# design.net
KiCad netlist of a schematic drawn in Altium Designer
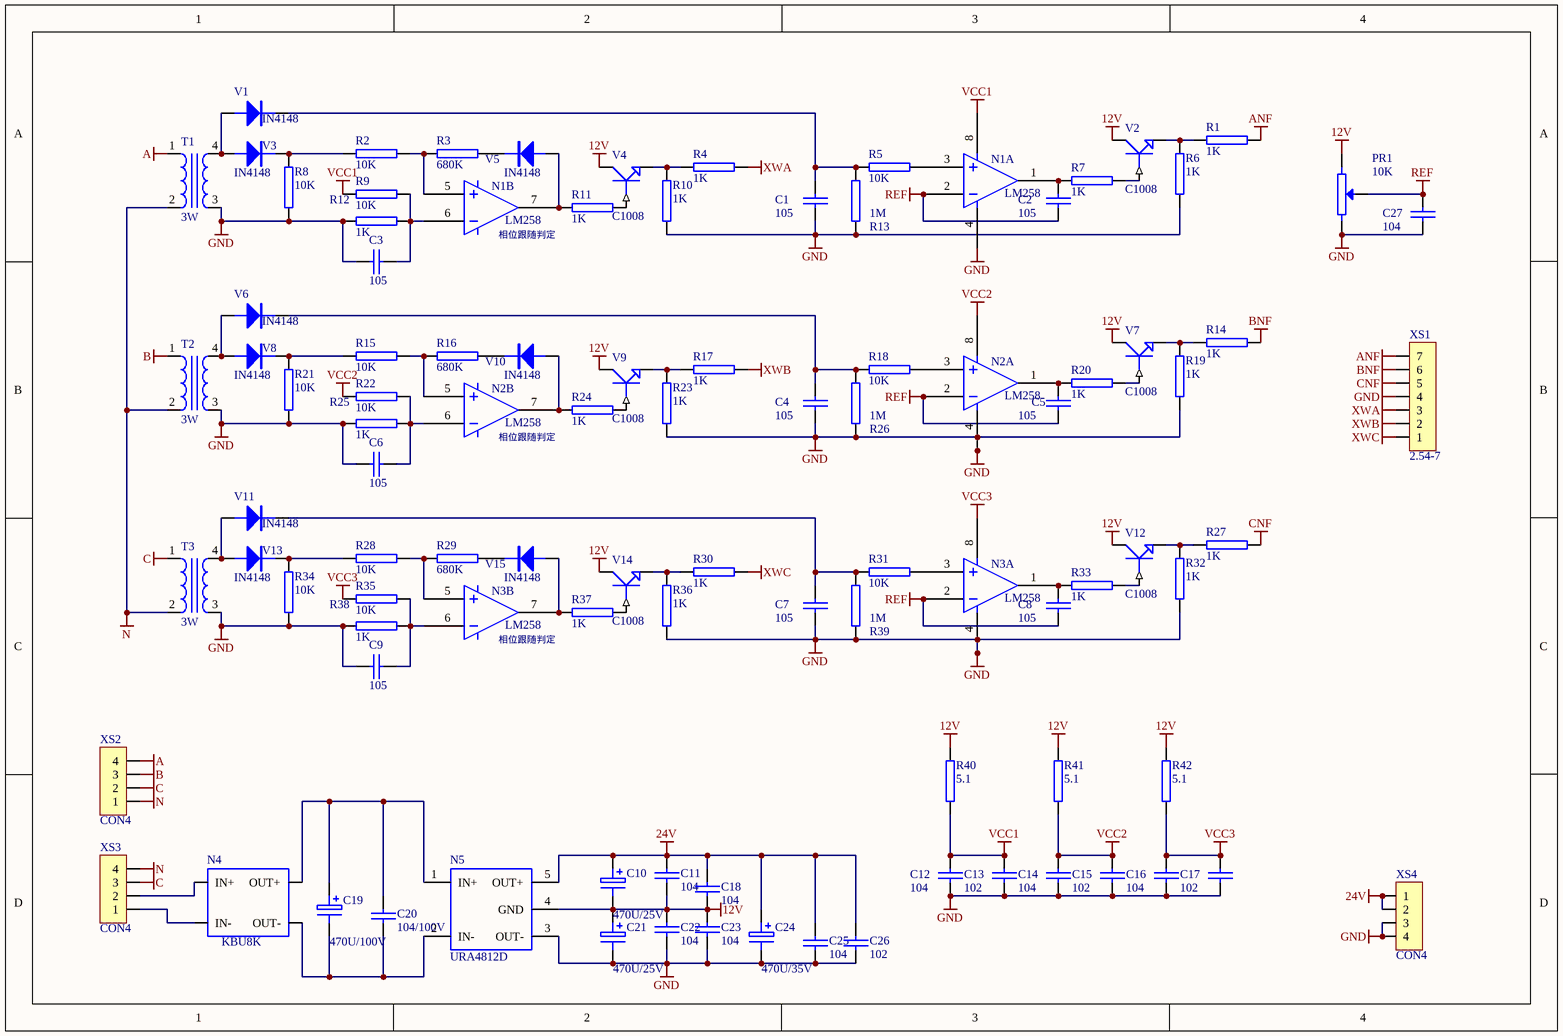
[diagram p0: 相位.SchDoc]

(export (version "E")
  (design (tool "Eeschema 10.0.6"))
  (components
    (comp (ref "C1") (value "105") (footprint "0805A") (libsource (lib "THT") (part "CAP")))
    (comp (ref "C2") (value "105") (footprint "0805A") (libsource (lib "THT") (part "CAP")))
    (comp (ref "C3") (value "105") (footprint "0805A") (libsource (lib "THT") (part "CAP")))
    (comp (ref "C4") (value "105") (footprint "0805A") (libsource (lib "THT") (part "CAP")))
    (comp (ref "C5") (value "105") (footprint "0805A") (libsource (lib "THT") (part "CAP")))
    (comp (ref "C6") (value "105") (footprint "0805A") (libsource (lib "THT") (part "CAP")))
    (comp (ref "C7") (value "105") (footprint "0805A") (libsource (lib "THT") (part "CAP")))
    (comp (ref "C8") (value "105") (footprint "0805A") (libsource (lib "THT") (part "CAP")))
    (comp (ref "C9") (value "105") (footprint "0805A") (libsource (lib "THT") (part "CAP")))
    (comp (ref "C10") (value "470U/25V") (footprint "RB5/10") (libsource (lib "*") (part "ELECTRO1")))
    (comp (ref "C11") (value "104") (footprint "1206") (libsource (lib "THT") (part "CAP")))
    (comp (ref "C12") (value "104") (footprint "0805A") (libsource (lib "THT") (part "CAP")))
    (comp (ref "C13") (value "102") (footprint "0805A") (libsource (lib "THT") (part "CAP")))
    (comp (ref "C14") (value "104") (footprint "0805A") (libsource (lib "THT") (part "CAP")))
    (comp (ref "C15") (value "102") (footprint "0805A") (libsource (lib "THT") (part "CAP")))
    (comp (ref "C16") (value "104") (footprint "0805A") (libsource (lib "THT") (part "CAP")))
    (comp (ref "C17") (value "102") (footprint "0805A") (libsource (lib "THT") (part "CAP")))
    (comp (ref "C18") (value "104") (footprint "1206") (libsource (lib "THT") (part "CAP")))
    (comp (ref "C19") (value "470U/100V") (footprint "RB.2/.6") (libsource (lib "*") (part "ELECTRO1")))
    (comp (ref "C20") (value "104/100V") (footprint "RAD0.2") (libsource (lib "THT") (part "CAP")))
    (comp (ref "C21") (value "470U/25V") (footprint "RB5/10") (libsource (lib "*") (part "ELECTRO1")))
    (comp (ref "C22") (value "104") (footprint "1206") (libsource (lib "THT") (part "CAP")))
    (comp (ref "C23") (value "104") (footprint "1206") (libsource (lib "THT") (part "CAP")))
    (comp (ref "C24") (value "470U/35V") (footprint "RB5/10") (libsource (lib "*") (part "ELECTRO1")))
    (comp (ref "C25") (value "104") (footprint "1206") (libsource (lib "THT") (part "CAP")))
    (comp (ref "C26") (value "102") (footprint "1206") (libsource (lib "THT") (part "CAP")))
    (comp (ref "C27") (value "104") (footprint "0805A") (libsource (lib "THT") (part "CAP")))
    (comp (ref "N1") (value "LM258") (footprint "SO-8") (libsource (lib "*") (part "LF353")))
    (comp (ref "N2") (value "LM258") (footprint "SO-8") (libsource (lib "*") (part "LF353")))
    (comp (ref "N3") (value "LM258") (footprint "SO-8") (libsource (lib "*") (part "LF353")))
    (comp (ref "N4") (value "KBU8K") (libsource (lib "THT") (part "DC-DC")))
    (comp (ref "N5") (value "URA4812D") (footprint "URA48") (libsource (lib "TH1") (part "YND5")))
    (comp (ref "PR1") (value "10K") (footprint "3224") (libsource (lib "TH1") (part "POT")))
    (comp (ref "R1") (value "1K") (footprint "0805A") (libsource (lib "THT") (part "RES2")))
    (comp (ref "R2") (value "10K") (footprint "0805A") (libsource (lib "THT") (part "RES2")))
    (comp (ref "R3") (value "680K") (footprint "0805A") (libsource (lib "THT") (part "RES2")))
    (comp (ref "R4") (value "1K") (footprint "0805A") (libsource (lib "THT") (part "RES2")))
    (comp (ref "R5") (value "10K") (footprint "0805A") (libsource (lib "THT") (part "RES2")))
    (comp (ref "R6") (value "1K") (footprint "0805A") (libsource (lib "THT") (part "RES2")))
    (comp (ref "R7") (value "1K") (footprint "0805A") (libsource (lib "THT") (part "RES2")))
    (comp (ref "R8") (value "10K") (footprint "0805A") (libsource (lib "THT") (part "RES2")))
    (comp (ref "R9") (value "10K") (footprint "0805A") (libsource (lib "THT") (part "RES2")))
    (comp (ref "R10") (value "1K") (footprint "0805A") (libsource (lib "THT") (part "RES2")))
    (comp (ref "R11") (value "1K") (footprint "0805A") (libsource (lib "THT") (part "RES2")))
    (comp (ref "R12") (value "1K") (footprint "0805A") (libsource (lib "THT") (part "RES2")))
    (comp (ref "R13") (value "1M") (footprint "0805A") (libsource (lib "THT") (part "RES2")))
    (comp (ref "R14") (value "1K") (footprint "0805A") (libsource (lib "THT") (part "RES2")))
    (comp (ref "R15") (value "10K") (footprint "0805A") (libsource (lib "THT") (part "RES2")))
    (comp (ref "R16") (value "680K") (footprint "0805A") (libsource (lib "THT") (part "RES2")))
    (comp (ref "R17") (value "1K") (footprint "0805A") (libsource (lib "THT") (part "RES2")))
    (comp (ref "R18") (value "10K") (footprint "0805A") (libsource (lib "THT") (part "RES2")))
    (comp (ref "R19") (value "1K") (footprint "0805A") (libsource (lib "THT") (part "RES2")))
    (comp (ref "R20") (value "1K") (footprint "0805A") (libsource (lib "THT") (part "RES2")))
    (comp (ref "R21") (value "10K") (footprint "0805A") (libsource (lib "THT") (part "RES2")))
    (comp (ref "R22") (value "10K") (footprint "0805A") (libsource (lib "THT") (part "RES2")))
    (comp (ref "R23") (value "1K") (footprint "0805A") (libsource (lib "THT") (part "RES2")))
    (comp (ref "R24") (value "1K") (footprint "0805A") (libsource (lib "THT") (part "RES2")))
    (comp (ref "R25") (value "1K") (footprint "0805A") (libsource (lib "THT") (part "RES2")))
    (comp (ref "R26") (value "1M") (footprint "0805A") (libsource (lib "THT") (part "RES2")))
    (comp (ref "R27") (value "1K") (footprint "0805A") (libsource (lib "THT") (part "RES2")))
    (comp (ref "R28") (value "10K") (footprint "0805A") (libsource (lib "THT") (part "RES2")))
    (comp (ref "R29") (value "680K") (footprint "0805A") (libsource (lib "THT") (part "RES2")))
    (comp (ref "R30") (value "1K") (footprint "0805A") (libsource (lib "THT") (part "RES2")))
    (comp (ref "R31") (value "10K") (footprint "0805A") (libsource (lib "THT") (part "RES2")))
    (comp (ref "R32") (value "1K") (footprint "0805A") (libsource (lib "THT") (part "RES2")))
    (comp (ref "R33") (value "1K") (footprint "0805A") (libsource (lib "THT") (part "RES2")))
    (comp (ref "R34") (value "10K") (footprint "0805A") (libsource (lib "THT") (part "RES2")))
    (comp (ref "R35") (value "10K") (footprint "0805A") (libsource (lib "THT") (part "RES2")))
    (comp (ref "R36") (value "1K") (footprint "0805A") (libsource (lib "THT") (part "RES2")))
    (comp (ref "R37") (value "1K") (footprint "0805A") (libsource (lib "THT") (part "RES2")))
    (comp (ref "R38") (value "1K") (footprint "0805A") (libsource (lib "THT") (part "RES2")))
    (comp (ref "R39") (value "1M") (footprint "0805A") (libsource (lib "THT") (part "RES2")))
    (comp (ref "R40") (value "5.1") (footprint "0805A") (libsource (lib "THT") (part "RES2")))
    (comp (ref "R41") (value "5.1") (footprint "0805A") (libsource (lib "THT") (part "RES2")))
    (comp (ref "R42") (value "5.1") (footprint "0805A") (libsource (lib "THT") (part "RES2")))
    (comp (ref "T1") (value "3W") (footprint "EE35") (libsource (lib "TH1") (part "TRANS1")))
    (comp (ref "T2") (value "3W") (footprint "EE35") (libsource (lib "TH1") (part "TRANS1")))
    (comp (ref "T3") (value "3W") (footprint "EE35") (libsource (lib "TH1") (part "TRANS1")))
    (comp (ref "V1") (value "IN4148") (footprint "1206-D") (libsource (lib "THT") (part "DIODE1")))
    (comp (ref "V2") (value "C1008") (footprint "SOT-23") (libsource (lib "THT") (part "NPN1")))
    (comp (ref "V3") (value "IN4148") (footprint "1206-D") (libsource (lib "THT") (part "DIODE1")))
    (comp (ref "V4") (value "C1008") (footprint "SOT-23") (libsource (lib "THT") (part "NPN1")))
    (comp (ref "V5") (value "IN4148") (footprint "1206-D") (libsource (lib "THT") (part "DIODE1")))
    (comp (ref "V6") (value "IN4148") (footprint "1206-D") (libsource (lib "THT") (part "DIODE1")))
    (comp (ref "V7") (value "C1008") (footprint "SOT-23") (libsource (lib "THT") (part "NPN1")))
    (comp (ref "V8") (value "IN4148") (footprint "1206-D") (libsource (lib "THT") (part "DIODE1")))
    (comp (ref "V9") (value "C1008") (footprint "SOT-23") (libsource (lib "THT") (part "NPN1")))
    (comp (ref "V10") (value "IN4148") (footprint "1206-D") (libsource (lib "THT") (part "DIODE1")))
    (comp (ref "V11") (value "IN4148") (footprint "1206-D") (libsource (lib "THT") (part "DIODE1")))
    (comp (ref "V12") (value "C1008") (footprint "SOT-23") (libsource (lib "THT") (part "NPN1")))
    (comp (ref "V13") (value "IN4148") (footprint "1206-D") (libsource (lib "THT") (part "DIODE1")))
    (comp (ref "V14") (value "C1008") (footprint "SOT-23") (libsource (lib "THT") (part "NPN1")))
    (comp (ref "V15") (value "IN4148") (footprint "1206-D") (libsource (lib "THT") (part "DIODE1")))
    (comp (ref "XS1") (value "2.54-7") (footprint "SIP7") (libsource (lib "THT") (part "CON7")))
    (comp (ref "XS2") (value "CON4") (footprint "XS10A-4P") (libsource (lib "THT") (part "CON4")))
    (comp (ref "XS3") (value "CON4") (footprint "XS10A-4P") (libsource (lib "THT") (part "CON4")))
    (comp (ref "XS4") (value "CON4") (footprint "SIP4") (libsource (lib "") (part "CON4_1")))
  )
  (nets
    (net (code "1") (name "12V") (class "Default")
      (node (ref "C10") (pin "2") (pintype "passive"))
      (node (ref "C11") (pin "2") (pintype "passive"))
      (node (ref "C18") (pin "2") (pintype "passive"))
      (node (ref "C21") (pin "1") (pintype "passive"))
      (node (ref "C22") (pin "1") (pintype "passive"))
      (node (ref "C23") (pin "1") (pintype "passive"))
      (node (ref "N5") (pin "4") (pinfunction "GND_4") (pintype "passive"))
      (node (ref "PR1") (pin "2") (pinfunction "2_2") (pintype "passive"))
      (node (ref "R40") (pin "2") (pintype "passive"))
      (node (ref "R41") (pin "2") (pintype "passive"))
      (node (ref "R42") (pin "2") (pintype "passive"))
      (node (ref "V12") (pin "C") (pinfunction "C_C") (pintype "passive"))
      (node (ref "V14") (pin "C") (pinfunction "C_C") (pintype "passive"))
      (node (ref "V2") (pin "C") (pinfunction "C_C") (pintype "passive"))
      (node (ref "V4") (pin "C") (pinfunction "C_C") (pintype "passive"))
      (node (ref "V7") (pin "C") (pinfunction "C_C") (pintype "passive"))
      (node (ref "V9") (pin "C") (pinfunction "C_C") (pintype "passive"))
    )
    (net (code "2") (name "24V") (class "Default")
      (node (ref "C10") (pin "1") (pintype "passive"))
      (node (ref "C11") (pin "1") (pintype "passive"))
      (node (ref "C18") (pin "1") (pintype "passive"))
      (node (ref "C24") (pin "1") (pintype "passive"))
      (node (ref "C25") (pin "1") (pintype "passive"))
      (node (ref "C26") (pin "1") (pintype "passive"))
      (node (ref "N5") (pin "5") (pinfunction "OUT+_5") (pintype "passive"))
      (node (ref "XS4") (pin "1") (pinfunction "1_1") (pintype "passive"))
      (node (ref "XS4") (pin "2") (pinfunction "2_2") (pintype "passive"))
    )
    (net (code "3") (name "A") (class "Default")
      (node (ref "T1") (pin "1") (pinfunction "1_1") (pintype "passive"))
      (node (ref "XS2") (pin "4") (pinfunction "4_4") (pintype "passive"))
    )
    (net (code "4") (name "ANF") (class "Default")
      (node (ref "R1") (pin "2") (pintype "passive"))
      (node (ref "XS1") (pin "7") (pinfunction "7_7") (pintype "passive"))
    )
    (net (code "5") (name "B") (class "Default")
      (node (ref "T2") (pin "1") (pinfunction "1_1") (pintype "passive"))
      (node (ref "XS2") (pin "3") (pinfunction "3_3") (pintype "passive"))
    )
    (net (code "6") (name "BNF") (class "Default")
      (node (ref "R14") (pin "2") (pintype "passive"))
      (node (ref "XS1") (pin "6") (pinfunction "6_6") (pintype "passive"))
    )
    (net (code "7") (name "C") (class "Default")
      (node (ref "T3") (pin "1") (pinfunction "1_1") (pintype "passive"))
      (node (ref "XS2") (pin "2") (pinfunction "2_2") (pintype "passive"))
      (node (ref "XS3") (pin "3") (pinfunction "3_3") (pintype "passive"))
    )
    (net (code "8") (name "CNF") (class "Default")
      (node (ref "R27") (pin "2") (pintype "passive"))
      (node (ref "XS1") (pin "5") (pinfunction "5_5") (pintype "passive"))
    )
    (net (code "9") (name "GND") (class "Default")
      (node (ref "C1") (pin "1") (pintype "passive"))
      (node (ref "C12") (pin "1") (pintype "passive"))
      (node (ref "C13") (pin "1") (pintype "passive"))
      (node (ref "C14") (pin "1") (pintype "passive"))
      (node (ref "C15") (pin "1") (pintype "passive"))
      (node (ref "C16") (pin "1") (pintype "passive"))
      (node (ref "C17") (pin "1") (pintype "passive"))
      (node (ref "C21") (pin "2") (pintype "passive"))
      (node (ref "C22") (pin "2") (pintype "passive"))
      (node (ref "C23") (pin "2") (pintype "passive"))
      (node (ref "C24") (pin "2") (pintype "passive"))
      (node (ref "C25") (pin "2") (pintype "passive"))
      (node (ref "C26") (pin "2") (pintype "passive"))
      (node (ref "C27") (pin "1") (pintype "passive"))
      (node (ref "C3") (pin "2") (pintype "passive"))
      (node (ref "C4") (pin "1") (pintype "passive"))
      (node (ref "C6") (pin "2") (pintype "passive"))
      (node (ref "C7") (pin "1") (pintype "passive"))
      (node (ref "C9") (pin "2") (pintype "passive"))
      (node (ref "N1") (pin "4") (pintype "passive"))
      (node (ref "N2") (pin "4") (pintype "passive"))
      (node (ref "N3") (pin "4") (pintype "passive"))
      (node (ref "N5") (pin "3") (pinfunction "OUT-_3") (pintype "passive"))
      (node (ref "PR1") (pin "1") (pinfunction "1_1") (pintype "passive"))
      (node (ref "R10") (pin "1") (pintype "passive"))
      (node (ref "R12") (pin "1") (pintype "passive"))
      (node (ref "R13") (pin "2") (pintype "passive"))
      (node (ref "R19") (pin "1") (pintype "passive"))
      (node (ref "R21") (pin "1") (pintype "passive"))
      (node (ref "R23") (pin "1") (pintype "passive"))
      (node (ref "R25") (pin "1") (pintype "passive"))
      (node (ref "R26") (pin "2") (pintype "passive"))
      (node (ref "R32") (pin "1") (pintype "passive"))
      (node (ref "R34") (pin "1") (pintype "passive"))
      (node (ref "R36") (pin "1") (pintype "passive"))
      (node (ref "R38") (pin "1") (pintype "passive"))
      (node (ref "R39") (pin "2") (pintype "passive"))
      (node (ref "R6") (pin "1") (pintype "passive"))
      (node (ref "R8") (pin "1") (pintype "passive"))
      (node (ref "T1") (pin "3") (pinfunction "3_3") (pintype "passive"))
      (node (ref "T2") (pin "3") (pinfunction "3_3") (pintype "passive"))
      (node (ref "T3") (pin "3") (pinfunction "3_3") (pintype "passive"))
      (node (ref "XS1") (pin "4") (pinfunction "4_4") (pintype "passive"))
      (node (ref "XS4") (pin "3") (pinfunction "3_3") (pintype "passive"))
      (node (ref "XS4") (pin "4") (pinfunction "4_4") (pintype "passive"))
    )
    (net (code "10") (name "N") (class "Default")
      (node (ref "T1") (pin "2") (pinfunction "2_2") (pintype "passive"))
      (node (ref "T2") (pin "2") (pinfunction "2_2") (pintype "passive"))
      (node (ref "T3") (pin "2") (pinfunction "2_2") (pintype "passive"))
      (node (ref "XS2") (pin "1") (pinfunction "1_1") (pintype "passive"))
      (node (ref "XS3") (pin "4") (pinfunction "4_4") (pintype "passive"))
    )
    (net (code "11") (name "Net-(C1-Pad2)") (class "Default")
      (node (ref "C1") (pin "2") (pintype "passive"))
      (node (ref "R13") (pin "1") (pintype "passive"))
      (node (ref "R5") (pin "1") (pintype "passive"))
      (node (ref "V1") (pin "K") (pinfunction "K_K") (pintype "passive"))
    )
    (net (code "12") (name "Net-(C2-Pad2)") (class "Default")
      (node (ref "C2") (pin "2") (pintype "passive"))
      (node (ref "N1") (pin "1") (pintype "passive"))
      (node (ref "R7") (pin "1") (pintype "passive"))
    )
    (net (code "13") (name "Net-(C3-Pad1)") (class "Default")
      (node (ref "C3") (pin "1") (pintype "passive"))
      (node (ref "N1") (pin "6") (pintype "passive"))
      (node (ref "R12") (pin "2") (pintype "passive"))
      (node (ref "R9") (pin "2") (pintype "passive"))
    )
    (net (code "14") (name "Net-(C4-Pad2)") (class "Default")
      (node (ref "C4") (pin "2") (pintype "passive"))
      (node (ref "R18") (pin "1") (pintype "passive"))
      (node (ref "R26") (pin "1") (pintype "passive"))
      (node (ref "V6") (pin "K") (pinfunction "K_K") (pintype "passive"))
    )
    (net (code "15") (name "Net-(C5-Pad2)") (class "Default")
      (node (ref "C5") (pin "2") (pintype "passive"))
      (node (ref "N2") (pin "1") (pintype "passive"))
      (node (ref "R20") (pin "1") (pintype "passive"))
    )
    (net (code "16") (name "Net-(C6-Pad1)") (class "Default")
      (node (ref "C6") (pin "1") (pintype "passive"))
      (node (ref "N2") (pin "6") (pintype "passive"))
      (node (ref "R22") (pin "2") (pintype "passive"))
      (node (ref "R25") (pin "2") (pintype "passive"))
    )
    (net (code "17") (name "Net-(C7-Pad2)") (class "Default")
      (node (ref "C7") (pin "2") (pintype "passive"))
      (node (ref "R31") (pin "1") (pintype "passive"))
      (node (ref "R39") (pin "1") (pintype "passive"))
      (node (ref "V11") (pin "K") (pinfunction "K_K") (pintype "passive"))
    )
    (net (code "18") (name "Net-(C8-Pad2)") (class "Default")
      (node (ref "C8") (pin "2") (pintype "passive"))
      (node (ref "N3") (pin "1") (pintype "passive"))
      (node (ref "R33") (pin "1") (pintype "passive"))
    )
    (net (code "19") (name "Net-(C9-Pad1)") (class "Default")
      (node (ref "C9") (pin "1") (pintype "passive"))
      (node (ref "N3") (pin "6") (pintype "passive"))
      (node (ref "R35") (pin "2") (pintype "passive"))
      (node (ref "R38") (pin "2") (pintype "passive"))
    )
    (net (code "20") (name "Net-(N1-Pad3)") (class "Default")
      (node (ref "N1") (pin "3") (pintype "passive"))
      (node (ref "R5") (pin "2") (pintype "passive"))
    )
    (net (code "21") (name "Net-(N1-Pad5)") (class "Default")
      (node (ref "N1") (pin "5") (pintype "passive"))
      (node (ref "R2") (pin "2") (pintype "passive"))
      (node (ref "R3") (pin "2") (pintype "passive"))
    )
    (net (code "22") (name "Net-(N1-Pad7)") (class "Default")
      (node (ref "N1") (pin "7") (pintype "passive"))
      (node (ref "R11") (pin "1") (pintype "passive"))
      (node (ref "V5") (pin "A") (pinfunction "A_A") (pintype "passive"))
    )
    (net (code "23") (name "Net-(N2-Pad3)") (class "Default")
      (node (ref "N2") (pin "3") (pintype "passive"))
      (node (ref "R18") (pin "2") (pintype "passive"))
    )
    (net (code "24") (name "Net-(N2-Pad5)") (class "Default")
      (node (ref "N2") (pin "5") (pintype "passive"))
      (node (ref "R15") (pin "2") (pintype "passive"))
      (node (ref "R16") (pin "2") (pintype "passive"))
    )
    (net (code "25") (name "Net-(N2-Pad7)") (class "Default")
      (node (ref "N2") (pin "7") (pintype "passive"))
      (node (ref "R24") (pin "1") (pintype "passive"))
      (node (ref "V10") (pin "A") (pinfunction "A_A") (pintype "passive"))
    )
    (net (code "26") (name "Net-(N3-Pad3)") (class "Default")
      (node (ref "N3") (pin "3") (pintype "passive"))
      (node (ref "R31") (pin "2") (pintype "passive"))
    )
    (net (code "27") (name "Net-(N3-Pad5)") (class "Default")
      (node (ref "N3") (pin "5") (pintype "passive"))
      (node (ref "R28") (pin "2") (pintype "passive"))
      (node (ref "R29") (pin "2") (pintype "passive"))
    )
    (net (code "28") (name "Net-(N3-Pad7)") (class "Default")
      (node (ref "N3") (pin "7") (pintype "passive"))
      (node (ref "R37") (pin "1") (pintype "passive"))
      (node (ref "V15") (pin "A") (pinfunction "A_A") (pintype "passive"))
    )
    (net (code "29") (name "Net-(N4-PadIN+)") (class "Default")
      (node (ref "N4") (pin "IN+") (pinfunction "IN+_IN+") (pintype "passive"))
      (node (ref "XS3") (pin "2") (pinfunction "2_2") (pintype "passive"))
    )
    (net (code "30") (name "Net-(N4-PadIN-)") (class "Default")
      (node (ref "N4") (pin "IN-") (pinfunction "IN-_IN-") (pintype "passive"))
      (node (ref "XS3") (pin "1") (pinfunction "1_1") (pintype "passive"))
    )
    (net (code "31") (name "Net-(N5-IN+)") (class "Default")
      (node (ref "C19") (pin "1") (pintype "passive"))
      (node (ref "C20") (pin "1") (pintype "passive"))
      (node (ref "N4") (pin "OUT+") (pinfunction "OUT+_OUT+") (pintype "passive"))
      (node (ref "N5") (pin "1") (pinfunction "IN+_1") (pintype "passive"))
    )
    (net (code "32") (name "Net-(N5-IN-)") (class "Default")
      (node (ref "C19") (pin "2") (pintype "passive"))
      (node (ref "C20") (pin "2") (pintype "passive"))
      (node (ref "N4") (pin "OUT-") (pinfunction "OUT-_OUT-") (pintype "passive"))
      (node (ref "N5") (pin "2") (pinfunction "IN-_2") (pintype "passive"))
    )
    (net (code "33") (name "Net-(R1-Pad1)") (class "Default")
      (node (ref "R1") (pin "1") (pintype "passive"))
      (node (ref "R6") (pin "2") (pintype "passive"))
      (node (ref "V2") (pin "E") (pinfunction "E_E") (pintype "passive"))
    )
    (net (code "34") (name "Net-(R2-Pad1)") (class "Default")
      (node (ref "R2") (pin "1") (pintype "passive"))
      (node (ref "R8") (pin "2") (pintype "passive"))
      (node (ref "V3") (pin "K") (pinfunction "K_K") (pintype "passive"))
    )
    (net (code "35") (name "Net-(R3-Pad1)") (class "Default")
      (node (ref "R3") (pin "1") (pintype "passive"))
      (node (ref "V5") (pin "K") (pinfunction "K_K") (pintype "passive"))
    )
    (net (code "36") (name "Net-(R7-Pad2)") (class "Default")
      (node (ref "R7") (pin "2") (pintype "passive"))
      (node (ref "V2") (pin "B") (pinfunction "B_B") (pintype "input"))
    )
    (net (code "37") (name "Net-(R10-Pad2)") (class "Default")
      (node (ref "R10") (pin "2") (pintype "passive"))
      (node (ref "R4") (pin "1") (pintype "passive"))
      (node (ref "V4") (pin "E") (pinfunction "E_E") (pintype "passive"))
    )
    (net (code "38") (name "Net-(R11-Pad2)") (class "Default")
      (node (ref "R11") (pin "2") (pintype "passive"))
      (node (ref "V4") (pin "B") (pinfunction "B_B") (pintype "input"))
    )
    (net (code "39") (name "Net-(R14-Pad1)") (class "Default")
      (node (ref "R14") (pin "1") (pintype "passive"))
      (node (ref "R19") (pin "2") (pintype "passive"))
      (node (ref "V7") (pin "E") (pinfunction "E_E") (pintype "passive"))
    )
    (net (code "40") (name "Net-(R15-Pad1)") (class "Default")
      (node (ref "R15") (pin "1") (pintype "passive"))
      (node (ref "R21") (pin "2") (pintype "passive"))
      (node (ref "V8") (pin "K") (pinfunction "K_K") (pintype "passive"))
    )
    (net (code "41") (name "Net-(R16-Pad1)") (class "Default")
      (node (ref "R16") (pin "1") (pintype "passive"))
      (node (ref "V10") (pin "K") (pinfunction "K_K") (pintype "passive"))
    )
    (net (code "42") (name "Net-(R17-Pad1)") (class "Default")
      (node (ref "R17") (pin "1") (pintype "passive"))
      (node (ref "R23") (pin "2") (pintype "passive"))
      (node (ref "V9") (pin "E") (pinfunction "E_E") (pintype "passive"))
    )
    (net (code "43") (name "Net-(R20-Pad2)") (class "Default")
      (node (ref "R20") (pin "2") (pintype "passive"))
      (node (ref "V7") (pin "B") (pinfunction "B_B") (pintype "input"))
    )
    (net (code "44") (name "Net-(R24-Pad2)") (class "Default")
      (node (ref "R24") (pin "2") (pintype "passive"))
      (node (ref "V9") (pin "B") (pinfunction "B_B") (pintype "input"))
    )
    (net (code "45") (name "Net-(R27-Pad1)") (class "Default")
      (node (ref "R27") (pin "1") (pintype "passive"))
      (node (ref "R32") (pin "2") (pintype "passive"))
      (node (ref "V12") (pin "E") (pinfunction "E_E") (pintype "passive"))
    )
    (net (code "46") (name "Net-(R28-Pad1)") (class "Default")
      (node (ref "R28") (pin "1") (pintype "passive"))
      (node (ref "R34") (pin "2") (pintype "passive"))
      (node (ref "V13") (pin "K") (pinfunction "K_K") (pintype "passive"))
    )
    (net (code "47") (name "Net-(R29-Pad1)") (class "Default")
      (node (ref "R29") (pin "1") (pintype "passive"))
      (node (ref "V15") (pin "K") (pinfunction "K_K") (pintype "passive"))
    )
    (net (code "48") (name "Net-(R30-Pad1)") (class "Default")
      (node (ref "R30") (pin "1") (pintype "passive"))
      (node (ref "R36") (pin "2") (pintype "passive"))
      (node (ref "V14") (pin "E") (pinfunction "E_E") (pintype "passive"))
    )
    (net (code "49") (name "Net-(R33-Pad2)") (class "Default")
      (node (ref "R33") (pin "2") (pintype "passive"))
      (node (ref "V12") (pin "B") (pinfunction "B_B") (pintype "input"))
    )
    (net (code "50") (name "Net-(R37-Pad2)") (class "Default")
      (node (ref "R37") (pin "2") (pintype "passive"))
      (node (ref "V14") (pin "B") (pinfunction "B_B") (pintype "input"))
    )
    (net (code "51") (name "Net-(T1-Pad4)") (class "Default")
      (node (ref "T1") (pin "4") (pinfunction "4_4") (pintype "passive"))
      (node (ref "V1") (pin "A") (pinfunction "A_A") (pintype "passive"))
      (node (ref "V3") (pin "A") (pinfunction "A_A") (pintype "passive"))
    )
    (net (code "52") (name "Net-(T2-Pad4)") (class "Default")
      (node (ref "T2") (pin "4") (pinfunction "4_4") (pintype "passive"))
      (node (ref "V6") (pin "A") (pinfunction "A_A") (pintype "passive"))
      (node (ref "V8") (pin "A") (pinfunction "A_A") (pintype "passive"))
    )
    (net (code "53") (name "Net-(T3-Pad4)") (class "Default")
      (node (ref "T3") (pin "4") (pinfunction "4_4") (pintype "passive"))
      (node (ref "V11") (pin "A") (pinfunction "A_A") (pintype "passive"))
      (node (ref "V13") (pin "A") (pinfunction "A_A") (pintype "passive"))
    )
    (net (code "54") (name "REF") (class "Default")
      (node (ref "C2") (pin "1") (pintype "passive"))
      (node (ref "C27") (pin "2") (pintype "passive"))
      (node (ref "C5") (pin "1") (pintype "passive"))
      (node (ref "C8") (pin "1") (pintype "passive"))
      (node (ref "N1") (pin "2") (pintype "passive"))
      (node (ref "N2") (pin "2") (pintype "passive"))
      (node (ref "N3") (pin "2") (pintype "passive"))
      (node (ref "PR1") (pin "W") (pinfunction "W_W") (pintype "passive"))
    )
    (net (code "55") (name "VCC1") (class "Default")
      (node (ref "C12") (pin "2") (pintype "passive"))
      (node (ref "C13") (pin "2") (pintype "passive"))
      (node (ref "N1") (pin "8") (pintype "passive"))
      (node (ref "R40") (pin "1") (pintype "passive"))
      (node (ref "R9") (pin "1") (pintype "passive"))
    )
    (net (code "56") (name "VCC2") (class "Default")
      (node (ref "C14") (pin "2") (pintype "passive"))
      (node (ref "C15") (pin "2") (pintype "passive"))
      (node (ref "N2") (pin "8") (pintype "passive"))
      (node (ref "R22") (pin "1") (pintype "passive"))
      (node (ref "R41") (pin "1") (pintype "passive"))
    )
    (net (code "57") (name "VCC3") (class "Default")
      (node (ref "C16") (pin "2") (pintype "passive"))
      (node (ref "C17") (pin "2") (pintype "passive"))
      (node (ref "N3") (pin "8") (pintype "passive"))
      (node (ref "R35") (pin "1") (pintype "passive"))
      (node (ref "R42") (pin "1") (pintype "passive"))
    )
    (net (code "58") (name "XWA") (class "Default")
      (node (ref "R4") (pin "2") (pintype "passive"))
      (node (ref "XS1") (pin "3") (pinfunction "3_3") (pintype "passive"))
    )
    (net (code "59") (name "XWB") (class "Default")
      (node (ref "R17") (pin "2") (pintype "passive"))
      (node (ref "XS1") (pin "2") (pinfunction "2_2") (pintype "passive"))
    )
    (net (code "60") (name "XWC") (class "Default")
      (node (ref "R30") (pin "2") (pintype "passive"))
      (node (ref "XS1") (pin "1") (pinfunction "1_1") (pintype "passive"))
    )
  )
)
